# GP_LDO_Circuit_Sheet.net
KiCad netlist of a schematic drawn in Altium Designer
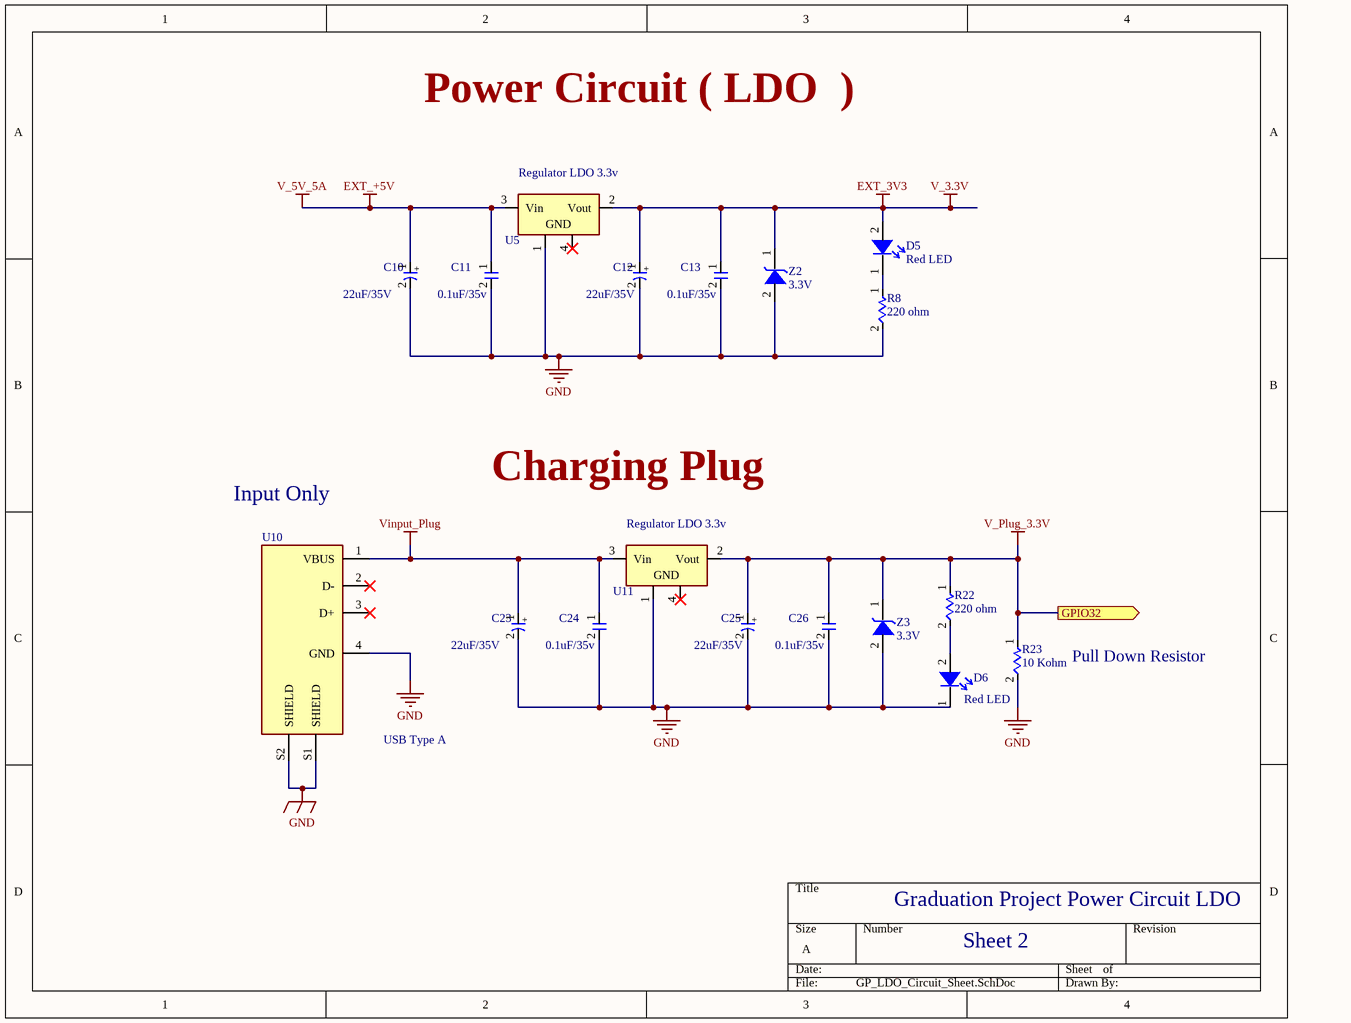
[diagram p0: GP_LDO_Circuit_Sheet.SchDoc]

(export (version "E")
  (design (tool "Eeschema 10.0.6"))
  (components
    (comp (ref "C10")
      (value "22uF/35V")
      (footprint "Electrolytic Capacitor 22UF")
      (description "Electrolytic Capacitor (22UF , 35V)SMD Radial Electrolytic Capacitor")
      (libsource (lib "GP_Integrated_Library") (part "Electrolytic Capacitor 22UF"))
    )
    (comp (ref "C11")
      (value "0.1uF/35v")
      (footprint "Capacitor 100nF")
      (description "Ceramic Capacitor (100nF , 50V) SMD (1206)")
      (libsource (lib "GP_Integrated_Library") (part "Capacitor 100nF"))
    )
    (comp (ref "C12")
      (value "22uF/35V")
      (footprint "Electrolytic Capacitor 22UF")
      (description "Electrolytic Capacitor (22UF , 35V)SMD Radial Electrolytic Capacitor")
      (libsource (lib "GP_Integrated_Library") (part "Electrolytic Capacitor 22UF"))
    )
    (comp (ref "C13")
      (value "0.1uF/35v")
      (footprint "Capacitor 100nF")
      (description "Ceramic Capacitor (100nF , 50V) SMD (1206)")
      (libsource (lib "GP_Integrated_Library") (part "Capacitor 100nF"))
    )
    (comp (ref "C23")
      (value "22uF/35V")
      (footprint "Electrolytic Capacitor 22UF")
      (description "Electrolytic Capacitor (22UF , 35V)SMD Radial Electrolytic Capacitor")
      (libsource (lib "GP_Integrated_Library") (part "Electrolytic Capacitor 22UF"))
    )
    (comp (ref "C24")
      (value "0.1uF/35v")
      (footprint "Capacitor 100nF")
      (description "Ceramic Capacitor (100nF , 50V) SMD (1206)")
      (libsource (lib "GP_Integrated_Library") (part "Capacitor 100nF"))
    )
    (comp (ref "C25")
      (value "22uF/35V")
      (footprint "Electrolytic Capacitor 22UF")
      (description "Electrolytic Capacitor (22UF , 35V)SMD Radial Electrolytic Capacitor")
      (libsource (lib "GP_Integrated_Library") (part "Electrolytic Capacitor 22UF"))
    )
    (comp (ref "C26")
      (value "0.1uF/35v")
      (footprint "Capacitor 100nF")
      (description "Ceramic Capacitor (100nF , 50V) SMD (1206)")
      (libsource (lib "GP_Integrated_Library") (part "Capacitor 100nF"))
    )
    (comp (ref "D5")
      (value "Red LED")
      (footprint "Red Led")
      (description "2012 Smd Led Red")
      (libsource (lib "GP_Integrated_Library") (part "Red LED"))
    )
    (comp (ref "D6")
      (value "Red LED")
      (footprint "Red Led")
      (description "2012 Smd Led Red")
      (libsource (lib "GP_Integrated_Library") (part "Red LED"))
    )
    (comp (ref "R8")
      (value "220 ohm")
      (footprint "Resistor 1Kohm")
      (description "SMD RESISTORS 200V-500V 1206")
      (libsource (lib "GP_Integrated_Library") (part "Resistor 1 Kohm"))
    )
    (comp (ref "R22")
      (value "220 ohm")
      (footprint "Resistor 1Kohm")
      (description "SMD RESISTORS 200V-500V 1206")
      (libsource (lib "GP_Integrated_Library") (part "Resistor 1 Kohm"))
    )
    (comp (ref "R23")
      (value "10 Kohm")
      (footprint "Resistor 1Kohm")
      (description "SMD RESISTORS 200V-500V 1206")
      (libsource (lib "GP_Integrated_Library") (part "Resistor 1 Kohm"))
    )
    (comp (ref "U5")
      (value "Regulator LDO 3.3v")
      (footprint "LDO 3.3V")
      (description "(+3.3V , 800mA ) Low-Dropout Voltage Regulator.(TO-220)")
      (libsource (lib "GP_Integrated_Library") (part "Regulator LDO 3.3v"))
    )
    (comp (ref "U10")
      (value "USB Type A")
      (footprint "USB Type A")
      (libsource (lib "GP_Integrated_Library") (part "USB Type A"))
    )
    (comp (ref "U11")
      (value "Regulator LDO 3.3v")
      (footprint "LDO 3.3V")
      (description "(+3.3V , 800mA ) Low-Dropout Voltage Regulator.(TO-220)")
      (libsource (lib "GP_Integrated_Library") (part "Regulator LDO 3.3v"))
    )
    (comp (ref "Z2")
      (value "3.3V")
      (footprint "Zener 3.3V Diode")
      (description "Zener Diodes ( 3.3V ) SMD SOD-123")
      (libsource (lib "GP_Integrated_Library") (part "Zener 3.3V"))
    )
    (comp (ref "Z3")
      (value "3.3V")
      (footprint "Zener 3.3V Diode")
      (description "Zener Diodes ( 3.3V ) SMD SOD-123")
      (libsource (lib "GP_Integrated_Library") (part "Zener 3.3V"))
    )
  )
  (nets
    (net (code "1") (name "EXT_+5V") (class "Default")
      (node (ref "C10") (pin "1") (pinfunction "Pin_1_1") (pintype "passive"))
      (node (ref "C11") (pin "1") (pinfunction "Pin_1_1") (pintype "passive"))
      (node (ref "U5") (pin "3") (pinfunction "Vin_3") (pintype "passive"))
    )
    (net (code "2") (name "EXT_3V3") (class "Default")
      (node (ref "C12") (pin "1") (pinfunction "Pin_1_1") (pintype "passive"))
      (node (ref "C13") (pin "1") (pinfunction "Pin_1_1") (pintype "passive"))
      (node (ref "D5") (pin "2") (pintype "passive"))
      (node (ref "U5") (pin "2") (pinfunction "Vout_2") (pintype "passive"))
      (node (ref "Z2") (pin "1") (pintype "passive"))
    )
    (net (code "3") (name "GND") (class "Default")
      (node (ref "C10") (pin "2") (pinfunction "Pin_2_2") (pintype "passive"))
      (node (ref "C11") (pin "2") (pinfunction "Pin_2_2") (pintype "passive"))
      (node (ref "C12") (pin "2") (pinfunction "Pin_2_2") (pintype "passive"))
      (node (ref "C13") (pin "2") (pinfunction "Pin_2_2") (pintype "passive"))
      (node (ref "C23") (pin "2") (pinfunction "Pin_2_2") (pintype "passive"))
      (node (ref "C24") (pin "2") (pinfunction "Pin_2_2") (pintype "passive"))
      (node (ref "C25") (pin "2") (pinfunction "Pin_2_2") (pintype "passive"))
      (node (ref "C26") (pin "2") (pinfunction "Pin_2_2") (pintype "passive"))
      (node (ref "D6") (pin "1") (pintype "passive"))
      (node (ref "R23") (pin "2") (pinfunction "pin_2_2") (pintype "passive"))
      (node (ref "R8") (pin "2") (pinfunction "pin_2_2") (pintype "passive"))
      (node (ref "U10") (pin "4") (pinfunction "GND_4") (pintype "passive"))
      (node (ref "U10") (pin "S1") (pinfunction "SHIELD_S1") (pintype "passive"))
      (node (ref "U10") (pin "S2") (pinfunction "SHIELD_S2") (pintype "passive"))
      (node (ref "U11") (pin "1") (pinfunction "GND_1") (pintype "passive"))
      (node (ref "U5") (pin "1") (pinfunction "GND_1") (pintype "passive"))
      (node (ref "Z2") (pin "2") (pintype "passive"))
      (node (ref "Z3") (pin "2") (pintype "passive"))
    )
    (net (code "4") (name "Net-(R8-Pin_1)") (class "Default")
      (node (ref "D5") (pin "1") (pintype "passive"))
      (node (ref "R8") (pin "1") (pinfunction "Pin_1_1") (pintype "passive"))
    )
    (net (code "5") (name "Net-(R22-pin_2)") (class "Default")
      (node (ref "D6") (pin "2") (pintype "passive"))
      (node (ref "R22") (pin "2") (pinfunction "pin_2_2") (pintype "passive"))
    )
    (net (code "6") (name "V_Plug_3.3V") (class "Default")
      (node (ref "C25") (pin "1") (pinfunction "Pin_1_1") (pintype "passive"))
      (node (ref "C26") (pin "1") (pinfunction "Pin_1_1") (pintype "passive"))
      (node (ref "R22") (pin "1") (pinfunction "Pin_1_1") (pintype "passive"))
      (node (ref "R23") (pin "1") (pinfunction "Pin_1_1") (pintype "passive"))
      (node (ref "U11") (pin "2") (pinfunction "Vout_2") (pintype "passive"))
      (node (ref "Z3") (pin "1") (pintype "passive"))
    )
    (net (code "7") (name "Vinput_Plug") (class "Default")
      (node (ref "C23") (pin "1") (pinfunction "Pin_1_1") (pintype "passive"))
      (node (ref "C24") (pin "1") (pinfunction "Pin_1_1") (pintype "passive"))
      (node (ref "U10") (pin "1") (pinfunction "VBUS_1") (pintype "power_in"))
      (node (ref "U11") (pin "3") (pinfunction "Vin_3") (pintype "passive"))
    )
    (net (code "8") (name "unconnected-(U5-GND-Pad4)") (class "Default")
      (node (ref "U5") (pin "4") (pinfunction "GND_4") (pintype "passive+no_connect"))
    )
    (net (code "9") (name "unconnected-(U10-D+-Pad3)") (class "Default")
      (node (ref "U10") (pin "3") (pinfunction "D+_3") (pintype "passive+no_connect"))
    )
    (net (code "10") (name "unconnected-(U10-D--Pad2)") (class "Default")
      (node (ref "U10") (pin "2") (pinfunction "D-_2") (pintype "power_in+no_connect"))
    )
    (net (code "11") (name "unconnected-(U11-GND-Pad4)") (class "Default")
      (node (ref "U11") (pin "4") (pinfunction "GND_4") (pintype "passive+no_connect"))
    )
  )
)
